# CPS2_CN7_Adapter_V1_1.net
KiCad netlist of a schematic drawn in EAGLE
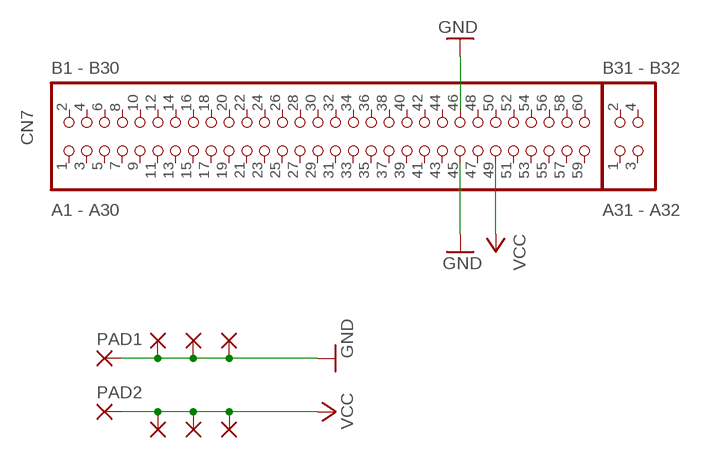
[diagram p0: schematic, sheet 1]

(export (version "E")
  (design (tool "Eeschema 10.0.6"))
  (components
    (comp (ref "JP1")
      (value "PINHD-2X30")
      (footprint "eagle-import:2X30")
      (libsource (lib "eagle-import") (part "PINHD-2X30"))
    )
    (comp (ref "JP2")
      (value "PINHD-2X2")
      (footprint "eagle-import:2X02")
      (libsource (lib "eagle-import") (part "PINHD-2X2"))
    )
    (comp (ref "PAD1")
      (value "SMD2")
      (footprint "eagle-import:SMD1,27-2,54")
      (libsource (lib "eagle-import") (part "SMD2"))
    )
    (comp (ref "PAD2")
      (value "SMD2")
      (footprint "eagle-import:SMD1,27-2,54")
      (libsource (lib "eagle-import") (part "SMD2"))
    )
    (comp (ref "PAD3")
      (value "SMD2")
      (footprint "eagle-import:SMD1,27-2,54")
      (libsource (lib "eagle-import") (part "SMD2"))
    )
    (comp (ref "PAD4")
      (value "SMD2")
      (footprint "eagle-import:SMD1,27-2,54")
      (libsource (lib "eagle-import") (part "SMD2"))
    )
    (comp (ref "PAD5")
      (value "SMD2")
      (footprint "eagle-import:SMD1,27-2,54")
      (libsource (lib "eagle-import") (part "SMD2"))
    )
    (comp (ref "PAD6")
      (value "SMD2")
      (footprint "eagle-import:SMD1,27-2,54")
      (libsource (lib "eagle-import") (part "SMD2"))
    )
    (comp (ref "PAD7")
      (value "SMD2")
      (footprint "eagle-import:SMD1,27-2,54")
      (libsource (lib "eagle-import") (part "SMD2"))
    )
    (comp (ref "PAD8")
      (value "SMD2")
      (footprint "eagle-import:SMD1,27-2,54")
      (libsource (lib "eagle-import") (part "SMD2"))
    )
  )
  (nets
    (net (code "1") (name "GND") (class "Default")
      (node (ref "JP1") (pin "45") (pinfunction "45_45") (pintype "passive"))
      (node (ref "JP1") (pin "46") (pinfunction "46_46") (pintype "passive"))
      (node (ref "PAD1") (pin "1") (pinfunction "P_1") (pintype "passive"))
      (node (ref "PAD3") (pin "1") (pinfunction "P_1") (pintype "passive"))
      (node (ref "PAD5") (pin "1") (pinfunction "P_1") (pintype "passive"))
      (node (ref "PAD6") (pin "1") (pinfunction "P_1") (pintype "passive"))
    )
    (net (code "2") (name "VCC") (class "Default")
      (node (ref "JP1") (pin "49") (pinfunction "49_49") (pintype "passive"))
      (node (ref "PAD2") (pin "1") (pinfunction "P_1") (pintype "passive"))
      (node (ref "PAD4") (pin "1") (pinfunction "P_1") (pintype "passive"))
      (node (ref "PAD7") (pin "1") (pinfunction "P_1") (pintype "passive"))
      (node (ref "PAD8") (pin "1") (pinfunction "P_1") (pintype "passive"))
    )
    (net (code "3") (name "unconnected-(JP1-Pad1)") (class "Default")
      (node (ref "JP1") (pin "1") (pinfunction "1_1") (pintype "passive"))
    )
    (net (code "4") (name "unconnected-(JP1-Pad2)") (class "Default")
      (node (ref "JP1") (pin "2") (pinfunction "2_2") (pintype "passive"))
    )
    (net (code "5") (name "unconnected-(JP1-Pad3)") (class "Default")
      (node (ref "JP1") (pin "3") (pinfunction "3_3") (pintype "passive"))
    )
    (net (code "6") (name "unconnected-(JP1-Pad4)") (class "Default")
      (node (ref "JP1") (pin "4") (pinfunction "4_4") (pintype "passive"))
    )
    (net (code "7") (name "unconnected-(JP1-Pad5)") (class "Default")
      (node (ref "JP1") (pin "5") (pinfunction "5_5") (pintype "passive"))
    )
    (net (code "8") (name "unconnected-(JP1-Pad6)") (class "Default")
      (node (ref "JP1") (pin "6") (pinfunction "6_6") (pintype "passive"))
    )
    (net (code "9") (name "unconnected-(JP1-Pad7)") (class "Default")
      (node (ref "JP1") (pin "7") (pinfunction "7_7") (pintype "passive"))
    )
    (net (code "10") (name "unconnected-(JP1-Pad8)") (class "Default")
      (node (ref "JP1") (pin "8") (pinfunction "8_8") (pintype "passive"))
    )
    (net (code "11") (name "unconnected-(JP1-Pad9)") (class "Default")
      (node (ref "JP1") (pin "9") (pinfunction "9_9") (pintype "passive"))
    )
    (net (code "12") (name "unconnected-(JP1-Pad10)") (class "Default")
      (node (ref "JP1") (pin "10") (pinfunction "10_10") (pintype "passive"))
    )
    (net (code "13") (name "unconnected-(JP1-Pad11)") (class "Default")
      (node (ref "JP1") (pin "11") (pinfunction "11_11") (pintype "passive"))
    )
    (net (code "14") (name "unconnected-(JP1-Pad12)") (class "Default")
      (node (ref "JP1") (pin "12") (pinfunction "12_12") (pintype "passive"))
    )
    (net (code "15") (name "unconnected-(JP1-Pad13)") (class "Default")
      (node (ref "JP1") (pin "13") (pinfunction "13_13") (pintype "passive"))
    )
    (net (code "16") (name "unconnected-(JP1-Pad14)") (class "Default")
      (node (ref "JP1") (pin "14") (pinfunction "14_14") (pintype "passive"))
    )
    (net (code "17") (name "unconnected-(JP1-Pad15)") (class "Default")
      (node (ref "JP1") (pin "15") (pinfunction "15_15") (pintype "passive"))
    )
    (net (code "18") (name "unconnected-(JP1-Pad16)") (class "Default")
      (node (ref "JP1") (pin "16") (pinfunction "16_16") (pintype "passive"))
    )
    (net (code "19") (name "unconnected-(JP1-Pad17)") (class "Default")
      (node (ref "JP1") (pin "17") (pinfunction "17_17") (pintype "passive"))
    )
    (net (code "20") (name "unconnected-(JP1-Pad18)") (class "Default")
      (node (ref "JP1") (pin "18") (pinfunction "18_18") (pintype "passive"))
    )
    (net (code "21") (name "unconnected-(JP1-Pad19)") (class "Default")
      (node (ref "JP1") (pin "19") (pinfunction "19_19") (pintype "passive"))
    )
    (net (code "22") (name "unconnected-(JP1-Pad20)") (class "Default")
      (node (ref "JP1") (pin "20") (pinfunction "20_20") (pintype "passive"))
    )
    (net (code "23") (name "unconnected-(JP1-Pad21)") (class "Default")
      (node (ref "JP1") (pin "21") (pinfunction "21_21") (pintype "passive"))
    )
    (net (code "24") (name "unconnected-(JP1-Pad22)") (class "Default")
      (node (ref "JP1") (pin "22") (pinfunction "22_22") (pintype "passive"))
    )
    (net (code "25") (name "unconnected-(JP1-Pad23)") (class "Default")
      (node (ref "JP1") (pin "23") (pinfunction "23_23") (pintype "passive"))
    )
    (net (code "26") (name "unconnected-(JP1-Pad24)") (class "Default")
      (node (ref "JP1") (pin "24") (pinfunction "24_24") (pintype "passive"))
    )
    (net (code "27") (name "unconnected-(JP1-Pad25)") (class "Default")
      (node (ref "JP1") (pin "25") (pinfunction "25_25") (pintype "passive"))
    )
    (net (code "28") (name "unconnected-(JP1-Pad26)") (class "Default")
      (node (ref "JP1") (pin "26") (pinfunction "26_26") (pintype "passive"))
    )
    (net (code "29") (name "unconnected-(JP1-Pad27)") (class "Default")
      (node (ref "JP1") (pin "27") (pinfunction "27_27") (pintype "passive"))
    )
    (net (code "30") (name "unconnected-(JP1-Pad28)") (class "Default")
      (node (ref "JP1") (pin "28") (pinfunction "28_28") (pintype "passive"))
    )
    (net (code "31") (name "unconnected-(JP1-Pad29)") (class "Default")
      (node (ref "JP1") (pin "29") (pinfunction "29_29") (pintype "passive"))
    )
    (net (code "32") (name "unconnected-(JP1-Pad30)") (class "Default")
      (node (ref "JP1") (pin "30") (pinfunction "30_30") (pintype "passive"))
    )
    (net (code "33") (name "unconnected-(JP1-Pad31)") (class "Default")
      (node (ref "JP1") (pin "31") (pinfunction "31_31") (pintype "passive"))
    )
    (net (code "34") (name "unconnected-(JP1-Pad32)") (class "Default")
      (node (ref "JP1") (pin "32") (pinfunction "32_32") (pintype "passive"))
    )
    (net (code "35") (name "unconnected-(JP1-Pad33)") (class "Default")
      (node (ref "JP1") (pin "33") (pinfunction "33_33") (pintype "passive"))
    )
    (net (code "36") (name "unconnected-(JP1-Pad34)") (class "Default")
      (node (ref "JP1") (pin "34") (pinfunction "34_34") (pintype "passive"))
    )
    (net (code "37") (name "unconnected-(JP1-Pad35)") (class "Default")
      (node (ref "JP1") (pin "35") (pinfunction "35_35") (pintype "passive"))
    )
    (net (code "38") (name "unconnected-(JP1-Pad36)") (class "Default")
      (node (ref "JP1") (pin "36") (pinfunction "36_36") (pintype "passive"))
    )
    (net (code "39") (name "unconnected-(JP1-Pad37)") (class "Default")
      (node (ref "JP1") (pin "37") (pinfunction "37_37") (pintype "passive"))
    )
    (net (code "40") (name "unconnected-(JP1-Pad38)") (class "Default")
      (node (ref "JP1") (pin "38") (pinfunction "38_38") (pintype "passive"))
    )
    (net (code "41") (name "unconnected-(JP1-Pad39)") (class "Default")
      (node (ref "JP1") (pin "39") (pinfunction "39_39") (pintype "passive"))
    )
    (net (code "42") (name "unconnected-(JP1-Pad40)") (class "Default")
      (node (ref "JP1") (pin "40") (pinfunction "40_40") (pintype "passive"))
    )
    (net (code "43") (name "unconnected-(JP1-Pad41)") (class "Default")
      (node (ref "JP1") (pin "41") (pinfunction "41_41") (pintype "passive"))
    )
    (net (code "44") (name "unconnected-(JP1-Pad42)") (class "Default")
      (node (ref "JP1") (pin "42") (pinfunction "42_42") (pintype "passive"))
    )
    (net (code "45") (name "unconnected-(JP1-Pad43)") (class "Default")
      (node (ref "JP1") (pin "43") (pinfunction "43_43") (pintype "passive"))
    )
    (net (code "46") (name "unconnected-(JP1-Pad44)") (class "Default")
      (node (ref "JP1") (pin "44") (pinfunction "44_44") (pintype "passive"))
    )
    (net (code "47") (name "unconnected-(JP1-Pad47)") (class "Default")
      (node (ref "JP1") (pin "47") (pinfunction "47_47") (pintype "passive"))
    )
    (net (code "48") (name "unconnected-(JP1-Pad48)") (class "Default")
      (node (ref "JP1") (pin "48") (pinfunction "48_48") (pintype "passive"))
    )
    (net (code "49") (name "unconnected-(JP1-Pad50)") (class "Default")
      (node (ref "JP1") (pin "50") (pinfunction "50_50") (pintype "passive"))
    )
    (net (code "50") (name "unconnected-(JP1-Pad51)") (class "Default")
      (node (ref "JP1") (pin "51") (pinfunction "51_51") (pintype "passive"))
    )
    (net (code "51") (name "unconnected-(JP1-Pad52)") (class "Default")
      (node (ref "JP1") (pin "52") (pinfunction "52_52") (pintype "passive"))
    )
    (net (code "52") (name "unconnected-(JP1-Pad53)") (class "Default")
      (node (ref "JP1") (pin "53") (pinfunction "53_53") (pintype "passive"))
    )
    (net (code "53") (name "unconnected-(JP1-Pad54)") (class "Default")
      (node (ref "JP1") (pin "54") (pinfunction "54_54") (pintype "passive"))
    )
    (net (code "54") (name "unconnected-(JP1-Pad55)") (class "Default")
      (node (ref "JP1") (pin "55") (pinfunction "55_55") (pintype "passive"))
    )
    (net (code "55") (name "unconnected-(JP1-Pad56)") (class "Default")
      (node (ref "JP1") (pin "56") (pinfunction "56_56") (pintype "passive"))
    )
    (net (code "56") (name "unconnected-(JP1-Pad57)") (class "Default")
      (node (ref "JP1") (pin "57") (pinfunction "57_57") (pintype "passive"))
    )
    (net (code "57") (name "unconnected-(JP1-Pad58)") (class "Default")
      (node (ref "JP1") (pin "58") (pinfunction "58_58") (pintype "passive"))
    )
    (net (code "58") (name "unconnected-(JP1-Pad59)") (class "Default")
      (node (ref "JP1") (pin "59") (pinfunction "59_59") (pintype "passive"))
    )
    (net (code "59") (name "unconnected-(JP1-Pad60)") (class "Default")
      (node (ref "JP1") (pin "60") (pinfunction "60_60") (pintype "passive"))
    )
    (net (code "60") (name "unconnected-(JP2-Pad1)") (class "Default")
      (node (ref "JP2") (pin "1") (pinfunction "1_1") (pintype "passive"))
    )
    (net (code "61") (name "unconnected-(JP2-Pad2)") (class "Default")
      (node (ref "JP2") (pin "2") (pinfunction "2_2") (pintype "passive"))
    )
    (net (code "62") (name "unconnected-(JP2-Pad3)") (class "Default")
      (node (ref "JP2") (pin "3") (pinfunction "3_3") (pintype "passive"))
    )
    (net (code "63") (name "unconnected-(JP2-Pad4)") (class "Default")
      (node (ref "JP2") (pin "4") (pinfunction "4_4") (pintype "passive"))
    )
  )
)
